# le_strum.net
KiCad netlist of a schematic drawn in EAGLE
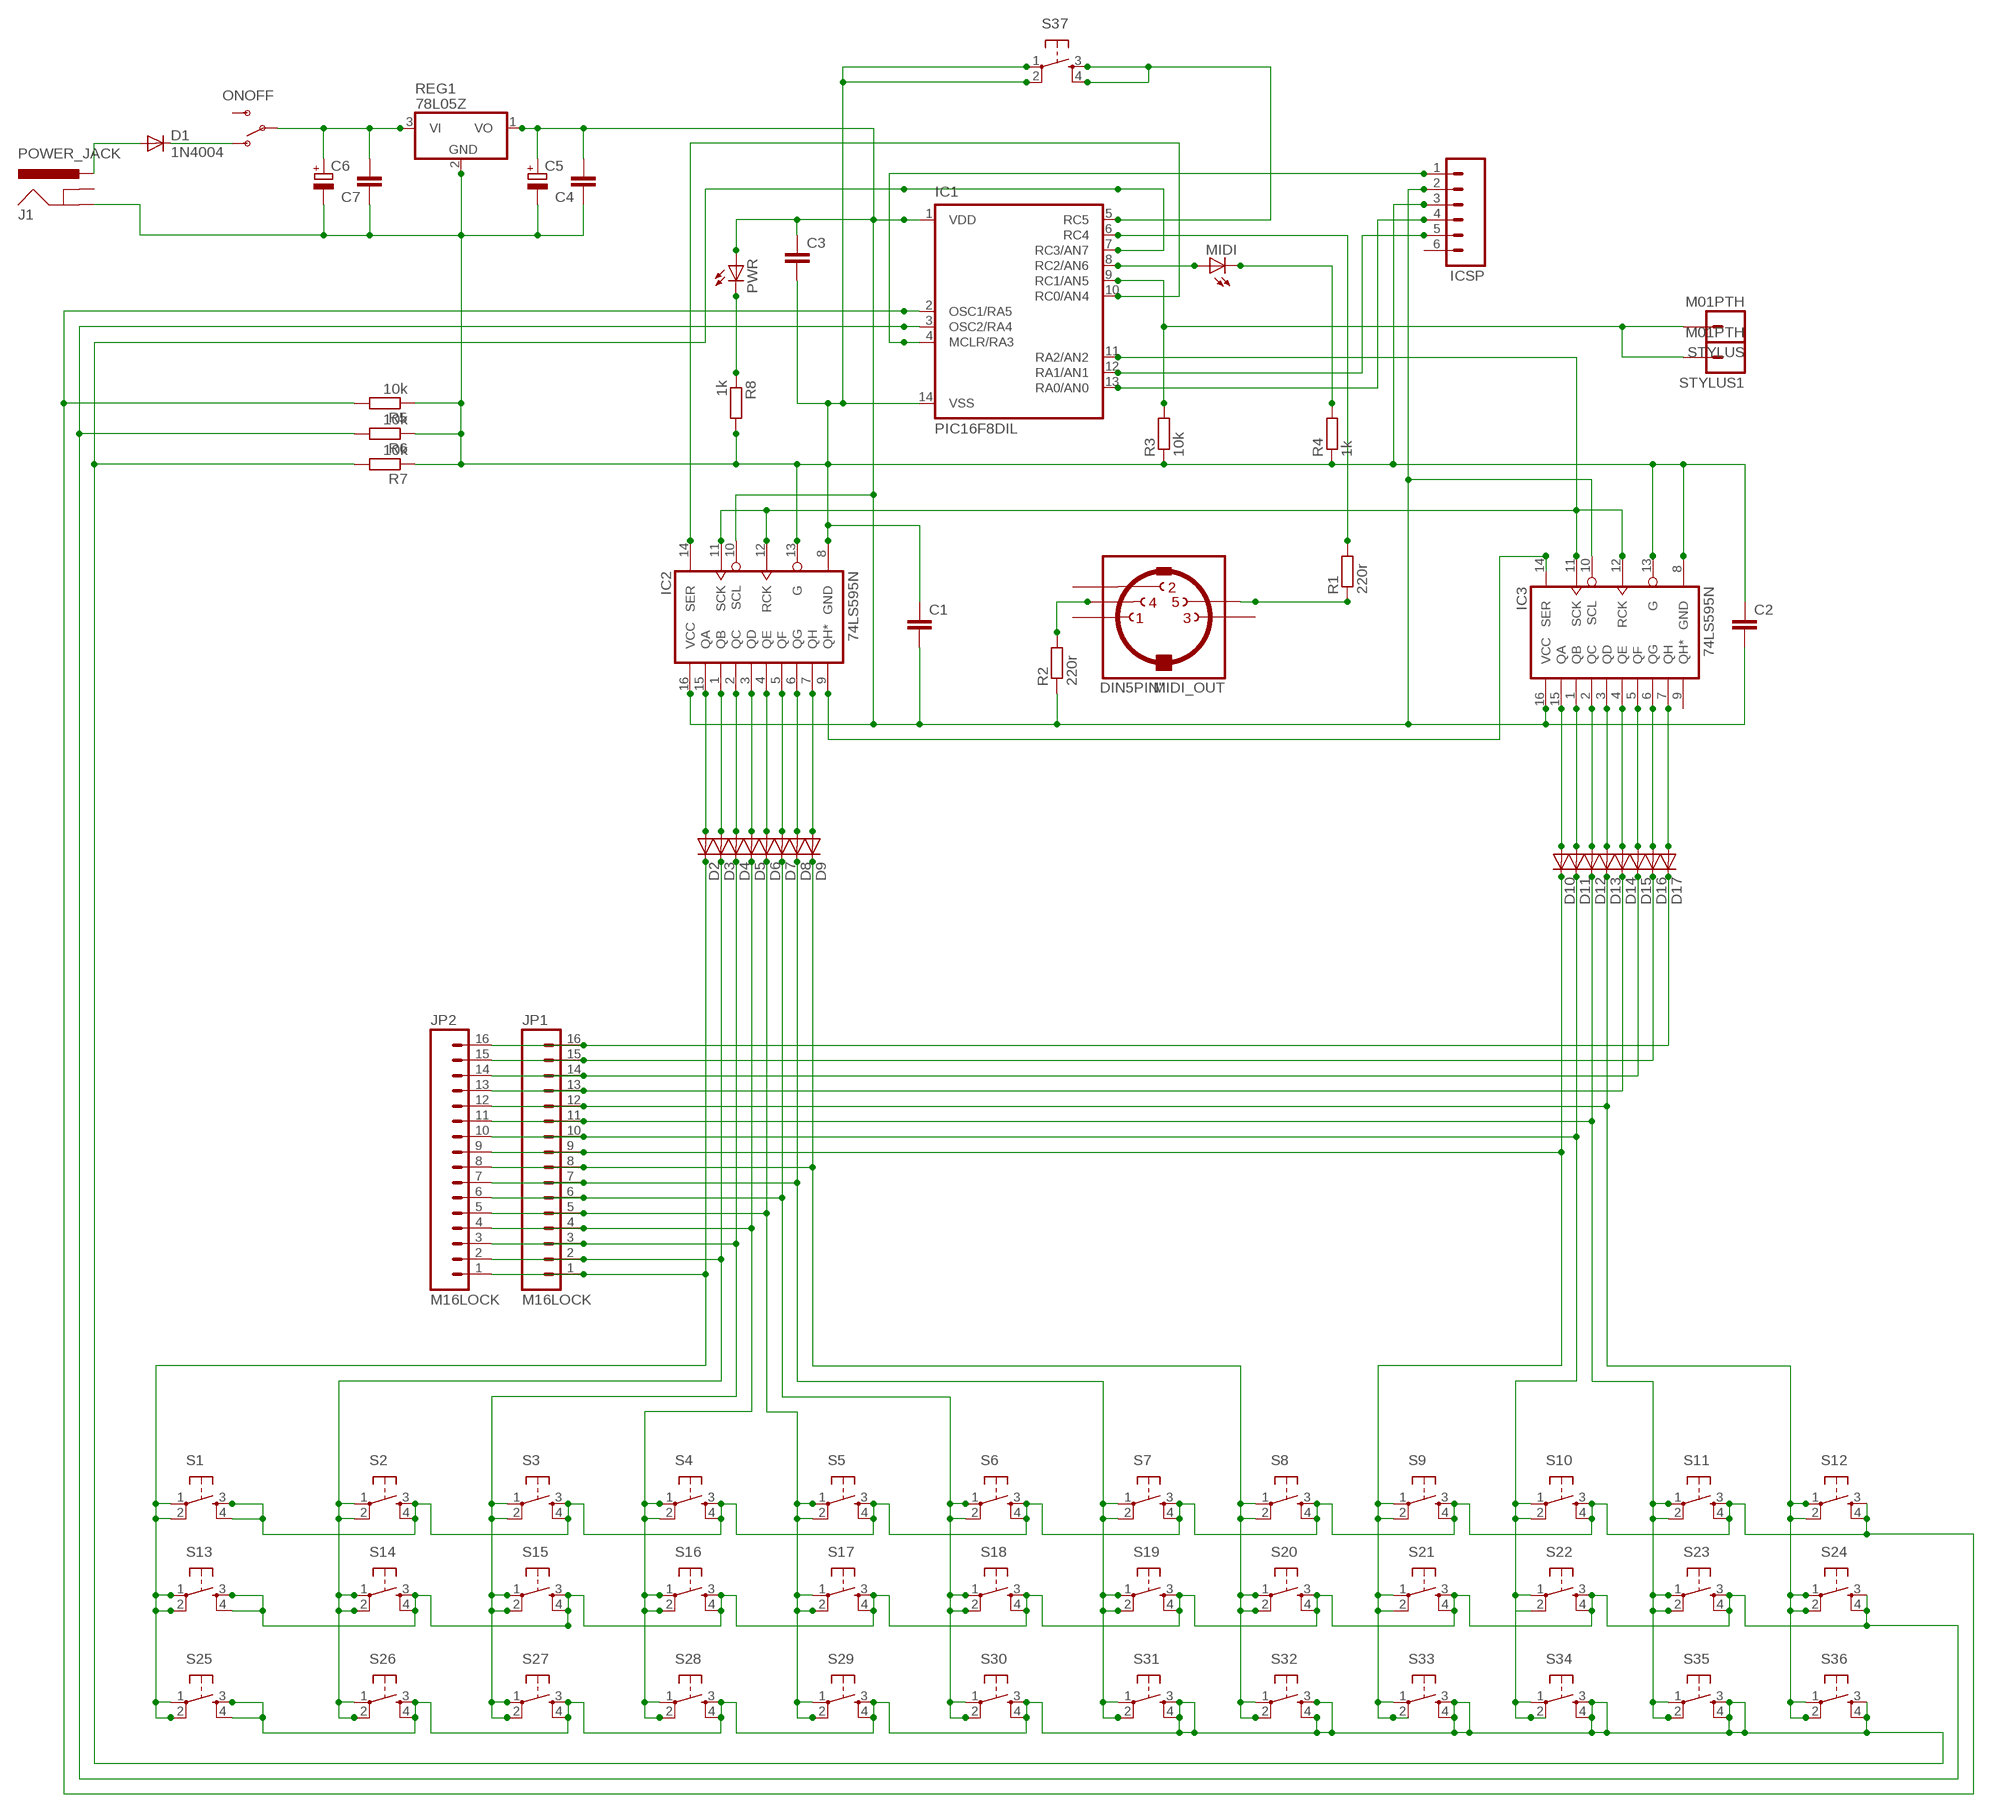
[diagram p0: schematic, sheet 1]

(export (version "E")
  (design (tool "Eeschema 10.0.6"))
  (components
    (comp (ref "C1")
      (value "C-EU025-024X044")
      (footprint "eagle-import:C025-024X044")
      (libsource (lib "eagle-import") (part "C-EU025-024X044"))
    )
    (comp (ref "C2")
      (value "C-EU025-024X044")
      (footprint "eagle-import:C025-024X044")
      (libsource (lib "eagle-import") (part "C-EU025-024X044"))
    )
    (comp (ref "C3")
      (value "C-EU025-024X044")
      (footprint "eagle-import:C025-024X044")
      (libsource (lib "eagle-import") (part "C-EU025-024X044"))
    )
    (comp (ref "C4")
      (value "C-EU025-024X044")
      (footprint "eagle-import:C025-024X044")
      (libsource (lib "eagle-import") (part "C-EU025-024X044"))
    )
    (comp (ref "C5")
      (value "CPOL-EUE2-5")
      (footprint "eagle-import:E2-5")
      (libsource (lib "eagle-import") (part "CPOL-EUE2-5"))
    )
    (comp (ref "C6")
      (value "CPOL-EUE2-5")
      (footprint "eagle-import:E2-5")
      (libsource (lib "eagle-import") (part "CPOL-EUE2-5"))
    )
    (comp (ref "C7")
      (value "C-EU025-024X044")
      (footprint "eagle-import:C025-024X044")
      (libsource (lib "eagle-import") (part "C-EU025-024X044"))
    )
    (comp (ref "D1")
      (value "1N4004")
      (footprint "eagle-import:DO41-10")
      (libsource (lib "eagle-import") (part "1N4004"))
    )
    (comp (ref "D2")
      (value "DIODE-D-5")
      (footprint "eagle-import:D-5")
      (libsource (lib "eagle-import") (part "DIODE-D-5"))
    )
    (comp (ref "D3")
      (value "DIODE-D-5")
      (footprint "eagle-import:D-5")
      (libsource (lib "eagle-import") (part "DIODE-D-5"))
    )
    (comp (ref "D4")
      (value "DIODE-D-5")
      (footprint "eagle-import:D-5")
      (libsource (lib "eagle-import") (part "DIODE-D-5"))
    )
    (comp (ref "D5")
      (value "DIODE-D-5")
      (footprint "eagle-import:D-5")
      (libsource (lib "eagle-import") (part "DIODE-D-5"))
    )
    (comp (ref "D6")
      (value "DIODE-D-5")
      (footprint "eagle-import:D-5")
      (libsource (lib "eagle-import") (part "DIODE-D-5"))
    )
    (comp (ref "D7")
      (value "DIODE-D-5")
      (footprint "eagle-import:D-5")
      (libsource (lib "eagle-import") (part "DIODE-D-5"))
    )
    (comp (ref "D8")
      (value "DIODE-D-5")
      (footprint "eagle-import:D-5")
      (libsource (lib "eagle-import") (part "DIODE-D-5"))
    )
    (comp (ref "D9")
      (value "DIODE-D-5")
      (footprint "eagle-import:D-5")
      (libsource (lib "eagle-import") (part "DIODE-D-5"))
    )
    (comp (ref "D10")
      (value "DIODE-D-5")
      (footprint "eagle-import:D-5")
      (libsource (lib "eagle-import") (part "DIODE-D-5"))
    )
    (comp (ref "D11")
      (value "DIODE-D-5")
      (footprint "eagle-import:D-5")
      (libsource (lib "eagle-import") (part "DIODE-D-5"))
    )
    (comp (ref "D12")
      (value "DIODE-D-5")
      (footprint "eagle-import:D-5")
      (libsource (lib "eagle-import") (part "DIODE-D-5"))
    )
    (comp (ref "D13")
      (value "DIODE-D-5")
      (footprint "eagle-import:D-5")
      (libsource (lib "eagle-import") (part "DIODE-D-5"))
    )
    (comp (ref "D14")
      (value "DIODE-D-5")
      (footprint "eagle-import:D-5")
      (libsource (lib "eagle-import") (part "DIODE-D-5"))
    )
    (comp (ref "D15")
      (value "DIODE-D-5")
      (footprint "eagle-import:D-5")
      (libsource (lib "eagle-import") (part "DIODE-D-5"))
    )
    (comp (ref "D16")
      (value "DIODE-D-5")
      (footprint "eagle-import:D-5")
      (libsource (lib "eagle-import") (part "DIODE-D-5"))
    )
    (comp (ref "D17")
      (value "DIODE-D-5")
      (footprint "eagle-import:D-5")
      (libsource (lib "eagle-import") (part "DIODE-D-5"))
    )
    (comp (ref "IC1")
      (value "PIC16F8DIL")
      (footprint "eagle-import:DIL14")
      (libsource (lib "eagle-import") (part "PIC16F8DIL"))
    )
    (comp (ref "IC2")
      (value "74LS595N")
      (footprint "eagle-import:DIL16")
      (libsource (lib "eagle-import") (part "74595NLS"))
    )
    (comp (ref "IC3")
      (value "74LS595N")
      (footprint "eagle-import:DIL16")
      (libsource (lib "eagle-import") (part "74595NLS"))
    )
    (comp (ref "ICSP")
      (value "M06SIP")
      (footprint "eagle-import:1X06")
      (libsource (lib "eagle-import") (part "M06SIP"))
    )
    (comp (ref "J1")
      (value "POWER_JACK")
      (footprint "eagle-import:POWER_JACK_PTH")
      (libsource (lib "eagle-import") (part "POWER_JACK"))
    )
    (comp (ref "JP1")
      (value "M16LOCK")
      (footprint "eagle-import:1X16_LOCK")
      (libsource (lib "eagle-import") (part "M16LOCK"))
    )
    (comp (ref "JP2")
      (value "M16LOCK")
      (footprint "eagle-import:1X16_LOCK")
      (libsource (lib "eagle-import") (part "M16LOCK"))
    )
    (comp (ref "MIDI")
      (value "LED3MM")
      (footprint "eagle-import:LED3MM")
      (libsource (lib "eagle-import") (part "LED3MM"))
    )
    (comp (ref "MIDI_OUT")
      (value "DIN5PIN\"")
      (footprint "eagle-import:TRUCONN90")
      (libsource (lib "eagle-import") (part "DIN5PIN{dblquote}"))
    )
    (comp (ref "ONOFF")
      (value "SWITCH-SPSTPTH")
      (footprint "eagle-import:SWITCH-SPDT")
      (libsource (lib "eagle-import") (part "SWITCH-SPSTPTH"))
    )
    (comp (ref "PWR")
      (value "LED3MM")
      (footprint "eagle-import:LED3MM")
      (libsource (lib "eagle-import") (part "LED3MM"))
    )
    (comp (ref "R1")
      (value "220r")
      (footprint "eagle-import:0207_7")
      (libsource (lib "eagle-import") (part "R-EU_0207/7"))
    )
    (comp (ref "R2")
      (value "220r")
      (footprint "eagle-import:0207_7")
      (libsource (lib "eagle-import") (part "R-EU_0207/7"))
    )
    (comp (ref "R3")
      (value "10k")
      (footprint "eagle-import:0207_7")
      (libsource (lib "eagle-import") (part "R-EU_0207/7"))
    )
    (comp (ref "R4")
      (value "1k")
      (footprint "eagle-import:0207_7")
      (libsource (lib "eagle-import") (part "R-EU_0207/7"))
    )
    (comp (ref "R5")
      (value "10k")
      (footprint "eagle-import:0207_7")
      (libsource (lib "eagle-import") (part "R-EU_0207/7"))
    )
    (comp (ref "R6")
      (value "10k")
      (footprint "eagle-import:0207_7")
      (libsource (lib "eagle-import") (part "R-EU_0207/7"))
    )
    (comp (ref "R7")
      (value "10k")
      (footprint "eagle-import:0207_7")
      (libsource (lib "eagle-import") (part "R-EU_0207/7"))
    )
    (comp (ref "R8")
      (value "1k")
      (footprint "eagle-import:0207_7")
      (libsource (lib "eagle-import") (part "R-EU_0207/7"))
    )
    (comp (ref "REG1")
      (value "78L05Z")
      (footprint "eagle-import:TO92")
      (libsource (lib "eagle-import") (part "78ZL05"))
    )
    (comp (ref "S1")
      (value "TAC_SWITCHPTH")
      (footprint "eagle-import:TACTILE-PTH")
      (libsource (lib "eagle-import") (part "TAC_SWITCHPTH"))
    )
    (comp (ref "S2")
      (value "TAC_SWITCHPTH")
      (footprint "eagle-import:TACTILE-PTH")
      (libsource (lib "eagle-import") (part "TAC_SWITCHPTH"))
    )
    (comp (ref "S3")
      (value "TAC_SWITCHPTH")
      (footprint "eagle-import:TACTILE-PTH")
      (libsource (lib "eagle-import") (part "TAC_SWITCHPTH"))
    )
    (comp (ref "S4")
      (value "TAC_SWITCHPTH")
      (footprint "eagle-import:TACTILE-PTH")
      (libsource (lib "eagle-import") (part "TAC_SWITCHPTH"))
    )
    (comp (ref "S5")
      (value "TAC_SWITCHPTH")
      (footprint "eagle-import:TACTILE-PTH")
      (libsource (lib "eagle-import") (part "TAC_SWITCHPTH"))
    )
    (comp (ref "S6")
      (value "TAC_SWITCHPTH")
      (footprint "eagle-import:TACTILE-PTH")
      (libsource (lib "eagle-import") (part "TAC_SWITCHPTH"))
    )
    (comp (ref "S7")
      (value "TAC_SWITCHPTH")
      (footprint "eagle-import:TACTILE-PTH")
      (libsource (lib "eagle-import") (part "TAC_SWITCHPTH"))
    )
    (comp (ref "S8")
      (value "TAC_SWITCHPTH")
      (footprint "eagle-import:TACTILE-PTH")
      (libsource (lib "eagle-import") (part "TAC_SWITCHPTH"))
    )
    (comp (ref "S9")
      (value "TAC_SWITCHPTH")
      (footprint "eagle-import:TACTILE-PTH")
      (libsource (lib "eagle-import") (part "TAC_SWITCHPTH"))
    )
    (comp (ref "S10")
      (value "TAC_SWITCHPTH")
      (footprint "eagle-import:TACTILE-PTH")
      (libsource (lib "eagle-import") (part "TAC_SWITCHPTH"))
    )
    (comp (ref "S11")
      (value "TAC_SWITCHPTH")
      (footprint "eagle-import:TACTILE-PTH")
      (libsource (lib "eagle-import") (part "TAC_SWITCHPTH"))
    )
    (comp (ref "S12")
      (value "TAC_SWITCHPTH")
      (footprint "eagle-import:TACTILE-PTH")
      (libsource (lib "eagle-import") (part "TAC_SWITCHPTH"))
    )
    (comp (ref "S13")
      (value "TAC_SWITCHPTH")
      (footprint "eagle-import:TACTILE-PTH")
      (libsource (lib "eagle-import") (part "TAC_SWITCHPTH"))
    )
    (comp (ref "S14")
      (value "TAC_SWITCHPTH")
      (footprint "eagle-import:TACTILE-PTH")
      (libsource (lib "eagle-import") (part "TAC_SWITCHPTH"))
    )
    (comp (ref "S15")
      (value "TAC_SWITCHPTH")
      (footprint "eagle-import:TACTILE-PTH")
      (libsource (lib "eagle-import") (part "TAC_SWITCHPTH"))
    )
    (comp (ref "S16")
      (value "TAC_SWITCHPTH")
      (footprint "eagle-import:TACTILE-PTH")
      (libsource (lib "eagle-import") (part "TAC_SWITCHPTH"))
    )
    (comp (ref "S17")
      (value "TAC_SWITCHPTH")
      (footprint "eagle-import:TACTILE-PTH")
      (libsource (lib "eagle-import") (part "TAC_SWITCHPTH"))
    )
    (comp (ref "S18")
      (value "TAC_SWITCHPTH")
      (footprint "eagle-import:TACTILE-PTH")
      (libsource (lib "eagle-import") (part "TAC_SWITCHPTH"))
    )
    (comp (ref "S19")
      (value "TAC_SWITCHPTH")
      (footprint "eagle-import:TACTILE-PTH")
      (libsource (lib "eagle-import") (part "TAC_SWITCHPTH"))
    )
    (comp (ref "S20")
      (value "TAC_SWITCHPTH")
      (footprint "eagle-import:TACTILE-PTH")
      (libsource (lib "eagle-import") (part "TAC_SWITCHPTH"))
    )
    (comp (ref "S21")
      (value "TAC_SWITCHPTH")
      (footprint "eagle-import:TACTILE-PTH")
      (libsource (lib "eagle-import") (part "TAC_SWITCHPTH"))
    )
    (comp (ref "S22")
      (value "TAC_SWITCHPTH")
      (footprint "eagle-import:TACTILE-PTH")
      (libsource (lib "eagle-import") (part "TAC_SWITCHPTH"))
    )
    (comp (ref "S23")
      (value "TAC_SWITCHPTH")
      (footprint "eagle-import:TACTILE-PTH")
      (libsource (lib "eagle-import") (part "TAC_SWITCHPTH"))
    )
    (comp (ref "S24")
      (value "TAC_SWITCHPTH")
      (footprint "eagle-import:TACTILE-PTH")
      (libsource (lib "eagle-import") (part "TAC_SWITCHPTH"))
    )
    (comp (ref "S25")
      (value "TAC_SWITCHPTH")
      (footprint "eagle-import:TACTILE-PTH")
      (libsource (lib "eagle-import") (part "TAC_SWITCHPTH"))
    )
    (comp (ref "S26")
      (value "TAC_SWITCHPTH")
      (footprint "eagle-import:TACTILE-PTH")
      (libsource (lib "eagle-import") (part "TAC_SWITCHPTH"))
    )
    (comp (ref "S27")
      (value "TAC_SWITCHPTH")
      (footprint "eagle-import:TACTILE-PTH")
      (libsource (lib "eagle-import") (part "TAC_SWITCHPTH"))
    )
    (comp (ref "S28")
      (value "TAC_SWITCHPTH")
      (footprint "eagle-import:TACTILE-PTH")
      (libsource (lib "eagle-import") (part "TAC_SWITCHPTH"))
    )
    (comp (ref "S29")
      (value "TAC_SWITCHPTH")
      (footprint "eagle-import:TACTILE-PTH")
      (libsource (lib "eagle-import") (part "TAC_SWITCHPTH"))
    )
    (comp (ref "S30")
      (value "TAC_SWITCHPTH")
      (footprint "eagle-import:TACTILE-PTH")
      (libsource (lib "eagle-import") (part "TAC_SWITCHPTH"))
    )
    (comp (ref "S31")
      (value "TAC_SWITCHPTH")
      (footprint "eagle-import:TACTILE-PTH")
      (libsource (lib "eagle-import") (part "TAC_SWITCHPTH"))
    )
    (comp (ref "S32")
      (value "TAC_SWITCHPTH")
      (footprint "eagle-import:TACTILE-PTH")
      (libsource (lib "eagle-import") (part "TAC_SWITCHPTH"))
    )
    (comp (ref "S33")
      (value "TAC_SWITCHPTH")
      (footprint "eagle-import:TACTILE-PTH")
      (libsource (lib "eagle-import") (part "TAC_SWITCHPTH"))
    )
    (comp (ref "S34")
      (value "TAC_SWITCHPTH")
      (footprint "eagle-import:TACTILE-PTH")
      (libsource (lib "eagle-import") (part "TAC_SWITCHPTH"))
    )
    (comp (ref "S35")
      (value "TAC_SWITCHPTH")
      (footprint "eagle-import:TACTILE-PTH")
      (libsource (lib "eagle-import") (part "TAC_SWITCHPTH"))
    )
    (comp (ref "S36")
      (value "TAC_SWITCHPTH")
      (footprint "eagle-import:TACTILE-PTH")
      (libsource (lib "eagle-import") (part "TAC_SWITCHPTH"))
    )
    (comp (ref "S37")
      (value "TAC_SWITCHPTH")
      (footprint "eagle-import:TACTILE-PTH")
      (libsource (lib "eagle-import") (part "TAC_SWITCHPTH"))
    )
    (comp (ref "STYLUS")
      (value "M01PTH")
      (footprint "eagle-import:1X01")
      (libsource (lib "eagle-import") (part "M01PTH"))
    )
    (comp (ref "STYLUS1")
      (value "M01PTH")
      (footprint "eagle-import:1X01")
      (libsource (lib "eagle-import") (part "M01PTH"))
    )
  )
  (nets
    (net (code "1") (name "Net-(D1-PadA)") (class "Default")
      (node (ref "D1") (pin "A") (pinfunction "A_A") (pintype "passive"))
      (node (ref "J1") (pin "PWR") (pinfunction "PWR_PWR") (pintype "bidirectional"))
    )
    (net (code "2") (name "Net-(D2-PadC)") (class "Default")
      (node (ref "D2") (pin "C") (pinfunction "C_C") (pintype "passive"))
      (node (ref "JP1") (pin "1") (pinfunction "1_1") (pintype "passive"))
      (node (ref "JP2") (pin "1") (pinfunction "1_1") (pintype "passive"))
      (node (ref "S1") (pin "1") (pinfunction "1_1") (pintype "passive"))
      (node (ref "S1") (pin "2") (pinfunction "2_2") (pintype "passive"))
      (node (ref "S13") (pin "1") (pinfunction "1_1") (pintype "passive"))
      (node (ref "S13") (pin "2") (pinfunction "2_2") (pintype "passive"))
      (node (ref "S25") (pin "1") (pinfunction "1_1") (pintype "passive"))
      (node (ref "S25") (pin "2") (pinfunction "2_2") (pintype "passive"))
    )
    (net (code "3") (name "Net-(D3-PadC)") (class "Default")
      (node (ref "D3") (pin "C") (pinfunction "C_C") (pintype "passive"))
      (node (ref "JP1") (pin "2") (pinfunction "2_2") (pintype "passive"))
      (node (ref "JP2") (pin "2") (pinfunction "2_2") (pintype "passive"))
      (node (ref "S14") (pin "1") (pinfunction "1_1") (pintype "passive"))
      (node (ref "S14") (pin "2") (pinfunction "2_2") (pintype "passive"))
      (node (ref "S2") (pin "1") (pinfunction "1_1") (pintype "passive"))
      (node (ref "S2") (pin "2") (pinfunction "2_2") (pintype "passive"))
      (node (ref "S26") (pin "1") (pinfunction "1_1") (pintype "passive"))
      (node (ref "S26") (pin "2") (pinfunction "2_2") (pintype "passive"))
    )
    (net (code "4") (name "Net-(D4-PadC)") (class "Default")
      (node (ref "D4") (pin "C") (pinfunction "C_C") (pintype "passive"))
      (node (ref "JP1") (pin "3") (pinfunction "3_3") (pintype "passive"))
      (node (ref "JP2") (pin "3") (pinfunction "3_3") (pintype "passive"))
      (node (ref "S15") (pin "1") (pinfunction "1_1") (pintype "passive"))
      (node (ref "S15") (pin "2") (pinfunction "2_2") (pintype "passive"))
      (node (ref "S27") (pin "1") (pinfunction "1_1") (pintype "passive"))
      (node (ref "S27") (pin "2") (pinfunction "2_2") (pintype "passive"))
      (node (ref "S3") (pin "1") (pinfunction "1_1") (pintype "passive"))
      (node (ref "S3") (pin "2") (pinfunction "2_2") (pintype "passive"))
    )
    (net (code "5") (name "Net-(D5-PadC)") (class "Default")
      (node (ref "D5") (pin "C") (pinfunction "C_C") (pintype "passive"))
      (node (ref "JP1") (pin "4") (pinfunction "4_4") (pintype "passive"))
      (node (ref "JP2") (pin "4") (pinfunction "4_4") (pintype "passive"))
      (node (ref "S16") (pin "1") (pinfunction "1_1") (pintype "passive"))
      (node (ref "S16") (pin "2") (pinfunction "2_2") (pintype "passive"))
      (node (ref "S28") (pin "1") (pinfunction "1_1") (pintype "passive"))
      (node (ref "S28") (pin "2") (pinfunction "2_2") (pintype "passive"))
      (node (ref "S4") (pin "1") (pinfunction "1_1") (pintype "passive"))
      (node (ref "S4") (pin "2") (pinfunction "2_2") (pintype "passive"))
    )
    (net (code "6") (name "Net-(D6-PadC)") (class "Default")
      (node (ref "D6") (pin "C") (pinfunction "C_C") (pintype "passive"))
      (node (ref "JP1") (pin "5") (pinfunction "5_5") (pintype "passive"))
      (node (ref "JP2") (pin "5") (pinfunction "5_5") (pintype "passive"))
      (node (ref "S17") (pin "1") (pinfunction "1_1") (pintype "passive"))
      (node (ref "S17") (pin "2") (pinfunction "2_2") (pintype "passive"))
      (node (ref "S29") (pin "1") (pinfunction "1_1") (pintype "passive"))
      (node (ref "S29") (pin "2") (pinfunction "2_2") (pintype "passive"))
      (node (ref "S5") (pin "1") (pinfunction "1_1") (pintype "passive"))
      (node (ref "S5") (pin "2") (pinfunction "2_2") (pintype "passive"))
    )
    (net (code "7") (name "Net-(D7-PadC)") (class "Default")
      (node (ref "D7") (pin "C") (pinfunction "C_C") (pintype "passive"))
      (node (ref "JP1") (pin "6") (pinfunction "6_6") (pintype "passive"))
      (node (ref "JP2") (pin "6") (pinfunction "6_6") (pintype "passive"))
      (node (ref "S18") (pin "1") (pinfunction "1_1") (pintype "passive"))
      (node (ref "S18") (pin "2") (pinfunction "2_2") (pintype "passive"))
      (node (ref "S30") (pin "1") (pinfunction "1_1") (pintype "passive"))
      (node (ref "S30") (pin "2") (pinfunction "2_2") (pintype "passive"))
      (node (ref "S6") (pin "1") (pinfunction "1_1") (pintype "passive"))
      (node (ref "S6") (pin "2") (pinfunction "2_2") (pintype "passive"))
    )
    (net (code "8") (name "Net-(D8-PadC)") (class "Default")
      (node (ref "D8") (pin "C") (pinfunction "C_C") (pintype "passive"))
      (node (ref "JP1") (pin "7") (pinfunction "7_7") (pintype "passive"))
      (node (ref "JP2") (pin "7") (pinfunction "7_7") (pintype "passive"))
      (node (ref "S19") (pin "1") (pinfunction "1_1") (pintype "passive"))
      (node (ref "S19") (pin "2") (pinfunction "2_2") (pintype "passive"))
      (node (ref "S31") (pin "1") (pinfunction "1_1") (pintype "passive"))
      (node (ref "S31") (pin "2") (pinfunction "2_2") (pintype "passive"))
      (node (ref "S7") (pin "1") (pinfunction "1_1") (pintype "passive"))
      (node (ref "S7") (pin "2") (pinfunction "2_2") (pintype "passive"))
    )
    (net (code "9") (name "Net-(D9-PadC)") (class "Default")
      (node (ref "D9") (pin "C") (pinfunction "C_C") (pintype "passive"))
      (node (ref "JP1") (pin "8") (pinfunction "8_8") (pintype "passive"))
      (node (ref "JP2") (pin "8") (pinfunction "8_8") (pintype "passive"))
      (node (ref "S20") (pin "1") (pinfunction "1_1") (pintype "passive"))
      (node (ref "S20") (pin "2") (pinfunction "2_2") (pintype "passive"))
      (node (ref "S32") (pin "1") (pinfunction "1_1") (pintype "passive"))
      (node (ref "S32") (pin "2") (pinfunction "2_2") (pintype "passive"))
      (node (ref "S8") (pin "1") (pinfunction "1_1") (pintype "passive"))
      (node (ref "S8") (pin "2") (pinfunction "2_2") (pintype "passive"))
    )
    (net (code "10") (name "Net-(D10-PadC)") (class "Default")
      (node (ref "D10") (pin "C") (pinfunction "C_C") (pintype "passive"))
      (node (ref "JP1") (pin "9") (pinfunction "9_9") (pintype "passive"))
      (node (ref "JP2") (pin "9") (pinfunction "9_9") (pintype "passive"))
      (node (ref "S21") (pin "1") (pinfunction "1_1") (pintype "passive"))
      (node (ref "S21") (pin "2") (pinfunction "2_2") (pintype "passive"))
      (node (ref "S33") (pin "1") (pinfunction "1_1") (pintype "passive"))
      (node (ref "S33") (pin "2") (pinfunction "2_2") (pintype "passive"))
      (node (ref "S9") (pin "1") (pinfunction "1_1") (pintype "passive"))
      (node (ref "S9") (pin "2") (pinfunction "2_2") (pintype "passive"))
    )
    (net (code "11") (name "Net-(D11-PadC)") (class "Default")
      (node (ref "D11") (pin "C") (pinfunction "C_C") (pintype "passive"))
      (node (ref "JP1") (pin "10") (pinfunction "10_10") (pintype "passive"))
      (node (ref "JP2") (pin "10") (pinfunction "10_10") (pintype "passive"))
      (node (ref "S10") (pin "1") (pinfunction "1_1") (pintype "passive"))
      (node (ref "S10") (pin "2") (pinfunction "2_2") (pintype "passive"))
      (node (ref "S22") (pin "1") (pinfunction "1_1") (pintype "passive"))
      (node (ref "S22") (pin "2") (pinfunction "2_2") (pintype "passive"))
      (node (ref "S34") (pin "1") (pinfunction "1_1") (pintype "passive"))
      (node (ref "S34") (pin "2") (pinfunction "2_2") (pintype "passive"))
    )
    (net (code "12") (name "Net-(D12-PadC)") (class "Default")
      (node (ref "D12") (pin "C") (pinfunction "C_C") (pintype "passive"))
      (node (ref "JP1") (pin "11") (pinfunction "11_11") (pintype "passive"))
      (node (ref "JP2") (pin "11") (pinfunction "11_11") (pintype "passive"))
      (node (ref "S11") (pin "1") (pinfunction "1_1") (pintype "passive"))
      (node (ref "S11") (pin "2") (pinfunction "2_2") (pintype "passive"))
      (node (ref "S23") (pin "1") (pinfunction "1_1") (pintype "passive"))
      (node (ref "S23") (pin "2") (pinfunction "2_2") (pintype "passive"))
      (node (ref "S35") (pin "1") (pinfunction "1_1") (pintype "passive"))
      (node (ref "S35") (pin "2") (pinfunction "2_2") (pintype "passive"))
    )
    (net (code "13") (name "Net-(D13-PadC)") (class "Default")
      (node (ref "D13") (pin "C") (pinfunction "C_C") (pintype "passive"))
      (node (ref "JP1") (pin "12") (pinfunction "12_12") (pintype "passive"))
      (node (ref "JP2") (pin "12") (pinfunction "12_12") (pintype "passive"))
      (node (ref "S12") (pin "1") (pinfunction "1_1") (pintype "passive"))
      (node (ref "S12") (pin "2") (pinfunction "2_2") (pintype "passive"))
      (node (ref "S24") (pin "1") (pinfunction "1_1") (pintype "passive"))
      (node (ref "S24") (pin "2") (pinfunction "2_2") (pintype "passive"))
      (node (ref "S36") (pin "1") (pinfunction "1_1") (pintype "passive"))
      (node (ref "S36") (pin "2") (pinfunction "2_2") (pintype "passive"))
    )
    (net (code "14") (name "Net-(D14-PadC)") (class "Default")
      (node (ref "D14") (pin "C") (pinfunction "C_C") (pintype "passive"))
      (node (ref "JP1") (pin "13") (pinfunction "13_13") (pintype "passive"))
      (node (ref "JP2") (pin "13") (pinfunction "13_13") (pintype "passive"))
    )
    (net (code "15") (name "Net-(D15-PadC)") (class "Default")
      (node (ref "D15") (pin "C") (pinfunction "C_C") (pintype "passive"))
      (node (ref "JP1") (pin "14") (pinfunction "14_14") (pintype "passive"))
      (node (ref "JP2") (pin "14") (pinfunction "14_14") (pintype "passive"))
    )
    (net (code "16") (name "Net-(D16-PadC)") (class "Default")
      (node (ref "D16") (pin "C") (pinfunction "C_C") (pintype "passive"))
      (node (ref "JP1") (pin "15") (pinfunction "15_15") (pintype "passive"))
      (node (ref "JP2") (pin "15") (pinfunction "15_15") (pintype "passive"))
    )
    (net (code "17") (name "Net-(D17-PadC)") (class "Default")
      (node (ref "D17") (pin "C") (pinfunction "C_C") (pintype "passive"))
      (node (ref "JP1") (pin "16") (pinfunction "16_16") (pintype "passive"))
      (node (ref "JP2") (pin "16") (pinfunction "16_16") (pintype "passive"))
    )
    (net (code "18") (name "Net-(IC1-MCLR{slash}RA3)") (class "Default")
      (node (ref "IC1") (pin "4") (pinfunction "MCLR/RA3_4") (pintype "input"))
      (node (ref "ICSP") (pin "1") (pinfunction "1_1") (pintype "passive"))
    )
    (net (code "19") (name "Net-(IC1-OSC1{slash}RA5)") (class "Default")
      (node (ref "IC1") (pin "2") (pinfunction "OSC1/RA5_2") (pintype "input"))
      (node (ref "R5") (pin "2") (pinfunction "2_2") (pintype "passive"))
      (node (ref "S1") (pin "3") (pinfunction "3_3") (pintype "passive"))
      (node (ref "S1") (pin "4") (pinfunction "4_4") (pintype "passive"))
      (node (ref "S10") (pin "3") (pinfunction "3_3") (pintype "passive"))
      (node (ref "S10") (pin "4") (pinfunction "4_4") (pintype "passive"))
      (node (ref "S11") (pin "3") (pinfunction "3_3") (pintype "passive"))
      (node (ref "S11") (pin "4") (pinfunction "4_4") (pintype "passive"))
      (node (ref "S12") (pin "3") (pinfunction "3_3") (pintype "passive"))
      (node (ref "S12") (pin "4") (pinfunction "4_4") (pintype "passive"))
      (node (ref "S2") (pin "3") (pinfunction "3_3") (pintype "passive"))
      (node (ref "S2") (pin "4") (pinfunction "4_4") (pintype "passive"))
      (node (ref "S3") (pin "3") (pinfunction "3_3") (pintype "passive"))
      (node (ref "S3") (pin "4") (pinfunction "4_4") (pintype "passive"))
      (node (ref "S4") (pin "3") (pinfunction "3_3") (pintype "passive"))
      (node (ref "S4") (pin "4") (pinfunction "4_4") (pintype "passive"))
      (node (ref "S5") (pin "3") (pinfunction "3_3") (pintype "passive"))
      (node (ref "S5") (pin "4") (pinfunction "4_4") (pintype "passive"))
      (node (ref "S6") (pin "3") (pinfunction "3_3") (pintype "passive"))
      (node (ref "S6") (pin "4") (pinfunction "4_4") (pintype "passive"))
      (node (ref "S7") (pin "3") (pinfunction "3_3") (pintype "passive"))
      (node (ref "S7") (pin "4") (pinfunction "4_4") (pintype "passive"))
      (node (ref "S8") (pin "3") (pinfunction "3_3") (pintype "passive"))
      (node (ref "S8") (pin "4") (pinfunction "4_4") (pintype "passive"))
      (node (ref "S9") (pin "3") (pinfunction "3_3") (pintype "passive"))
      (node (ref "S9") (pin "4") (pinfunction "4_4") (pintype "passive"))
    )
    (net (code "20") (name "Net-(IC1-OSC2{slash}RA4)") (class "Default")
      (node (ref "IC1") (pin "3") (pinfunction "OSC2/RA4_3") (pintype "output"))
      (node (ref "R6") (pin "2") (pinfunction "2_2") (pintype "passive"))
      (node (ref "S13") (pin "3") (pinfunction "3_3") (pintype "passive"))
      (node (ref "S13") (pin "4") (pinfunction "4_4") (pintype "passive"))
      (node (ref "S14") (pin "3") (pinfunction "3_3") (pintype "passive"))
      (node (ref "S14") (pin "4") (pinfunction "4_4") (pintype "passive"))
      (node (ref "S15") (pin "3") (pinfunction "3_3") (pintype "passive"))
      (node (ref "S15") (pin "4") (pinfunction "4_4") (pintype "passive"))
      (node (ref "S16") (pin "3") (pinfunction "3_3") (pintype "passive"))
      (node (ref "S16") (pin "4") (pinfunction "4_4") (pintype "passive"))
      (node (ref "S17") (pin "3") (pinfunction "3_3") (pintype "passive"))
      (node (ref "S17") (pin "4") (pinfunction "4_4") (pintype "passive"))
      (node (ref "S18") (pin "3") (pinfunction "3_3") (pintype "passive"))
      (node (ref "S18") (pin "4") (pinfunction "4_4") (pintype "passive"))
      (node (ref "S19") (pin "3") (pinfunction "3_3") (pintype "passive"))
      (node (ref "S19") (pin "4") (pinfunction "4_4") (pintype "passive"))
      (node (ref "S20") (pin "3") (pinfunction "3_3") (pintype "passive"))
      (node (ref "S20") (pin "4") (pinfunction "4_4") (pintype "passive"))
      (node (ref "S21") (pin "3") (pinfunction "3_3") (pintype "passive"))
      (node (ref "S21") (pin "4") (pinfunction "4_4") (pintype "passive"))
      (node (ref "S22") (pin "3") (pinfunction "3_3") (pintype "passive"))
      (node (ref "S22") (pin "4") (pinfunction "4_4") (pintype "passive"))
      (node (ref "S23") (pin "3") (pinfunction "3_3") (pintype "passive"))
      (node (ref "S23") (pin "4") (pinfunction "4_4") (pintype "passive"))
      (node (ref "S24") (pin "3") (pinfunction "3_3") (pintype "passive"))
      (node (ref "S24") (pin "4") (pinfunction "4_4") (pintype "passive"))
    )
    (net (code "21") (name "Net-(IC1-RA0{slash}AN0)") (class "Default")
      (node (ref "IC1") (pin "13") (pinfunction "RA0/AN0_13") (pintype "bidirectional"))
      (node (ref "ICSP") (pin "4") (pinfunction "4_4") (pintype "passive"))
    )
    (net (code "22") (name "Net-(IC1-RA1{slash}AN1)") (class "Default")
      (node (ref "IC1") (pin "12") (pinfunction "RA1/AN1_12") (pintype "bidirectional"))
      (node (ref "ICSP") (pin "5") (pinfunction "5_5") (pintype "passive"))
    )
    (net (code "23") (name "Net-(IC1-RA2{slash}AN2)") (class "Default")
      (node (ref "IC1") (pin "11") (pinfunction "RA2/AN2_11") (pintype "bidirectional"))
      (node (ref "IC2") (pin "11") (pinfunction "SCK_11") (pintype "input"))
      (node (ref "IC2") (pin "12") (pinfunction "RCK_12") (pintype "input"))
      (node (ref "IC3") (pin "11") (pinfunction "SCK_11") (pintype "input"))
      (node (ref "IC3") (pin "12") (pinfunction "RCK_12") (pintype "input"))
    )
    (net (code "24") (name "Net-(IC1-RC0{slash}AN4)") (class "Default")
      (node (ref "IC1") (pin "10") (pinfunction "RC0/AN4_10") (pintype "bidirectional"))
      (node (ref "IC2") (pin "14") (pinfunction "SER_14") (pintype "input"))
    )
    (net (code "25") (name "Net-(IC1-RC1{slash}AN5)") (class "Default")
      (node (ref "IC1") (pin "9") (pinfunction "RC1/AN5_9") (pintype "bidirectional"))
      (node (ref "R3") (pin "2") (pinfunction "2_2") (pintype "passive"))
      (node (ref "STYLUS") (pin "1") (pinfunction "1_1") (pintype "passive"))
      (node (ref "STYLUS1") (pin "1") (pinfunction "1_1") (pintype "passive"))
    )
    (net (code "26") (name "Net-(IC1-RC2{slash}AN6)") (class "Default")
      (node (ref "IC1") (pin "8") (pinfunction "RC2/AN6_8") (pintype "bidirectional"))
      (node (ref "MIDI") (pin "A") (pinfunction "A_A") (pintype "passive"))
    )
    (net (code "27") (name "Net-(IC1-RC3{slash}AN7)") (class "Default")
      (node (ref "IC1") (pin "7") (pinfunction "RC3/AN7_7") (pintype "bidirectional"))
      (node (ref "R7") (pin "2") (pinfunction "2_2") (pintype "passive"))
      (node (ref "S25") (pin "3") (pinfunction "3_3") (pintype "passive"))
      (node (ref "S25") (pin "4") (pinfunction "4_4") (pintype "passive"))
      (node (ref "S26") (pin "3") (pinfunction "3_3") (pintype "passive"))
      (node (ref "S26") (pin "4") (pinfunction "4_4") (pintype "passive"))
      (node (ref "S27") (pin "3") (pinfunction "3_3") (pintype "passive"))
      (node (ref "S27") (pin "4") (pinfunction "4_4") (pintype "passive"))
      (node (ref "S28") (pin "3") (pinfunction "3_3") (pintype "passive"))
      (node (ref "S28") (pin "4") (pinfunction "4_4") (pintype "passive"))
      (node (ref "S29") (pin "3") (pinfunction "3_3") (pintype "passive"))
      (node (ref "S29") (pin "4") (pinfunction "4_4") (pintype "passive"))
      (node (ref "S30") (pin "3") (pinfunction "3_3") (pintype "passive"))
      (node (ref "S30") (pin "4") (pinfunction "4_4") (pintype "passive"))
      (node (ref "S31") (pin "3") (pinfunction "3_3") (pintype "passive"))
      (node (ref "S31") (pin "4") (pinfunction "4_4") (pintype "passive"))
      (node (ref "S32") (pin "3") (pinfunction "3_3") (pintype "passive"))
      (node (ref "S32") (pin "4") (pinfunction "4_4") (pintype "passive"))
      (node (ref "S33") (pin "3") (pinfunction "3_3") (pintype "passive"))
      (node (ref "S33") (pin "4") (pinfunction "4_4") (pintype "passive"))
      (node (ref "S34") (pin "3") (pinfunction "3_3") (pintype "passive"))
      (node (ref "S34") (pin "4") (pinfunction "4_4") (pintype "passive"))
      (node (ref "S35") (pin "3") (pinfunction "3_3") (pintype "passive"))
      (node (ref "S35") (pin "4") (pinfunction "4_4") (pintype "passive"))
      (node (ref "S36") (pin "3") (pinfunction "3_3") (pintype "passive"))
      (node (ref "S36") (pin "4") (pinfunction "4_4") (pintype "passive"))
    )
    (net (code "28") (name "Net-(IC1-RC4)") (class "Default")
      (node (ref "IC1") (pin "6") (pinfunction "RC4_6") (pintype "bidirectional"))
      (node (ref "R1") (pin "2") (pinfunction "2_2") (pintype "passive"))
    )
    (net (code "29") (name "Net-(IC1-RC5)") (class "Default")
      (node (ref "IC1") (pin "5") (pinfunction "RC5_5") (pintype "bidirectional"))
      (node (ref "S37") (pin "3") (pinfunction "3_3") (pintype "passive"))
      (node (ref "S37") (pin "4") (pinfunction "4_4") (pintype "passive"))
    )
    (net (code "30") (name "Net-(IC1-VDD)") (class "Default")
      (node (ref "C1") (pin "2") (pinfunction "2_2") (pintype "passive"))
      (node (ref "C2") (pin "2") (pinfunction "2_2") (pintype "passive"))
      (node (ref "C3") (pin "1") (pinfunction "1_1") (pintype "passive"))
      (node (ref "C4") (pin "2") (pinfunction "2_2") (pintype "passive"))
      (node (ref "C5") (pin "+") (pinfunction "+_+") (pintype "passive"))
      (node (ref "IC1") (pin "1") (pinfunction "VDD_1") (pintype "power_in"))
      (node (ref "IC2") (pin "10") (pinfunction "SCL_10") (pintype "input"))
      (node (ref "IC2") (pin "16") (pinfunction "VCC_16") (pintype "power_in"))
      (node (ref "IC3") (pin "10") (pinfunction "SCL_10") (pintype "input"))
      (node (ref "IC3") (pin "16") (pinfunction "VCC_16") (pintype "power_in"))
      (node (ref "ICSP") (pin "2") (pinfunction "2_2") (pintype "passive"))
      (node (ref "PWR") (pin "A") (pinfunction "A_A") (pintype "passive"))
      (node (ref "R2") (pin "1") (pinfunction "1_1") (pintype "passive"))
      (node (ref "REG1") (pin "1") (pinfunction "VO_1") (pintype "passive"))
    )
    (net (code "31") (name "Net-(IC1-VSS)") (class "Default")
      (node (ref "C1") (pin "1") (pinfunction "1_1") (pintype "passive"))
      (node (ref "C2") (pin "1") (pinfunction "1_1") (pintype "passive"))
      (node (ref "C3") (pin "2") (pinfunction "2_2") (pintype "passive"))
      (node (ref "C4") (pin "1") (pinfunction "1_1") (pintype "passive"))
      (node (ref "C5") (pin "-") (pinfunction "-_-") (pintype "passive"))
      (node (ref "C6") (pin "-") (pinfunction "-_-") (pintype "passive"))
      (node (ref "C7") (pin "1") (pinfunction "1_1") (pintype "passive"))
      (node (ref "IC1") (pin "14") (pinfunction "VSS_14") (pintype "power_in"))
      (node (ref "IC2") (pin "13") (pinfunction "G_13") (pintype "input"))
      (node (ref "IC2") (pin "8") (pinfunction "GND_8") (pintype "power_in"))
      (node (ref "IC3") (pin "13") (pinfunction "G_13") (pintype "input"))
      (node (ref "IC3") (pin "8") (pinfunction "GND_8") (pintype "power_in"))
      (node (ref "ICSP") (pin "3") (pinfunction "3_3") (pintype "passive"))
      (node (ref "J1") (pin "GND") (pinfunction "GND_GND") (pintype "bidirectional"))
      (node (ref "R3") (pin "1") (pinfunction "1_1") (pintype "passive"))
      (node (ref "R4") (pin "1") (pinfunction "1_1") (pintype "passive"))
      (node (ref "R5") (pin "1") (pinfunction "1_1") (pintype "passive"))
      (node (ref "R6") (pin "1") (pinfunction "1_1") (pintype "passive"))
      (node (ref "R7") (pin "1") (pinfunction "1_1") (pintype "passive"))
      (node (ref "R8") (pin "2") (pinfunction "2_2") (pintype "passive"))
      (node (ref "REG1") (pin "2") (pinfunction "GND_2") (pintype "passive"))
      (node (ref "S37") (pin "1") (pinfunction "1_1") (pintype "passive"))
      (node (ref "S37") (pin "2") (pinfunction "2_2") (pintype "passive"))
    )
    (net (code "32") (name "Net-(IC2-QA)") (class "Default")
      (node (ref "D2") (pin "A") (pinfunction "A_A") (pintype "passive"))
      (node (ref "IC2") (pin "15") (pinfunction "QA_15") (pintype "tri_state"))
    )
    (net (code "33") (name "Net-(IC2-QB)") (class "Default")
      (node (ref "D3") (pin "A") (pinfunction "A_A") (pintype "passive"))
      (node (ref "IC2") (pin "1") (pinfunction "QB_1") (pintype "tri_state"))
    )
    (net (code "34") (name "Net-(IC2-QC)") (class "Default")
      (node (ref "D4") (pin "A") (pinfunction "A_A") (pintype "passive"))
      (node (ref "IC2") (pin "2") (pinfunction "QC_2") (pintype "tri_state"))
    )
    (net (code "35") (name "Net-(IC2-QD)") (class "Default")
      (node (ref "D5") (pin "A") (pinfunction "A_A") (pintype "passive"))
      (node (ref "IC2") (pin "3") (pinfunction "QD_3") (pintype "tri_state"))
    )
    (net (code "36") (name "Net-(IC2-QE)") (class "Default")
      (node (ref "D6") (pin "A") (pinfunction "A_A") (pintype "passive"))
      (node (ref "IC2") (pin "4") (pinfunction "QE_4") (pintype "tri_state"))
    )
    (net (code "37") (name "Net-(IC2-QF)") (class "Default")
      (node (ref "D7") (pin "A") (pinfunction "A_A") (pintype "passive"))
      (node (ref "IC2") (pin "5") (pinfunction "QF_5") (pintype "tri_state"))
    )
    (net (code "38") (name "Net-(IC2-QG)") (class "Default")
      (node (ref "D8") (pin "A") (pinfunction "A_A") (pintype "passive"))
      (node (ref "IC2") (pin "6") (pinfunction "QG_6") (pintype "tri_state"))
    )
    (net (code "39") (name "Net-(IC2-QH)") (class "Default")
      (node (ref "D9") (pin "A") (pinfunction "A_A") (pintype "passive"))
      (node (ref "IC2") (pin "7") (pinfunction "QH_7") (pintype "tri_state"))
    )
    (net (code "40") (name "Net-(IC2-QH*)") (class "Default")
      (node (ref "IC2") (pin "9") (pinfunction "QH*_9") (pintype "tri_state"))
      (node (ref "IC3") (pin "14") (pinfunction "SER_14") (pintype "input"))
    )
    (net (code "41") (name "Net-(IC3-QA)") (class "Default")
      (node (ref "D10") (pin "A") (pinfunction "A_A") (pintype "passive"))
      (node (ref "IC3") (pin "15") (pinfunction "QA_15") (pintype "tri_state"))
    )
    (net (code "42") (name "Net-(IC3-QB)") (class "Default")
      (node (ref "D11") (pin "A") (pinfunction "A_A") (pintype "passive"))
      (node (ref "IC3") (pin "1") (pinfunction "QB_1") (pintype "tri_state"))
    )
    (net (code "43") (name "Net-(IC3-QC)") (class "Default")
      (node (ref "D12") (pin "A") (pinfunction "A_A") (pintype "passive"))
      (node (ref "IC3") (pin "2") (pinfunction "QC_2") (pintype "tri_state"))
    )
    (net (code "44") (name "Net-(IC3-QD)") (class "Default")
      (node (ref "D13") (pin "A") (pinfunction "A_A") (pintype "passive"))
      (node (ref "IC3") (pin "3") (pinfunction "QD_3") (pintype "tri_state"))
    )
    (net (code "45") (name "Net-(IC3-QE)") (class "Default")
      (node (ref "D14") (pin "A") (pinfunction "A_A") (pintype "passive"))
      (node (ref "IC3") (pin "4") (pinfunction "QE_4") (pintype "tri_state"))
    )
    (net (code "46") (name "Net-(IC3-QF)") (class "Default")
      (node (ref "D15") (pin "A") (pinfunction "A_A") (pintype "passive"))
      (node (ref "IC3") (pin "5") (pinfunction "QF_5") (pintype "tri_state"))
    )
    (net (code "47") (name "Net-(IC3-QG)") (class "Default")
      (node (ref "D16") (pin "A") (pinfunction "A_A") (pintype "passive"))
      (node (ref "IC3") (pin "6") (pinfunction "QG_6") (pintype "tri_state"))
    )
    (net (code "48") (name "Net-(IC3-QH)") (class "Default")
      (node (ref "D17") (pin "A") (pinfunction "A_A") (pintype "passive"))
      (node (ref "IC3") (pin "7") (pinfunction "QH_7") (pintype "tri_state"))
    )
    (net (code "49") (name "Net-(MIDI-C)") (class "Default")
      (node (ref "MIDI") (pin "K") (pinfunction "C_K") (pintype "passive"))
      (node (ref "R4") (pin "2") (pinfunction "2_2") (pintype "passive"))
    )
    (net (code "50") (name "Net-(MIDI_OUT-Pad4)") (class "Default")
      (node (ref "MIDI_OUT") (pin "4") (pinfunction "4_4") (pintype "passive"))
      (node (ref "R2") (pin "2") (pinfunction "2_2") (pintype "passive"))
    )
    (net (code "51") (name "Net-(MIDI_OUT-Pad5)") (class "Default")
      (node (ref "MIDI_OUT") (pin "5") (pinfunction "5_5") (pintype "passive"))
      (node (ref "R1") (pin "1") (pinfunction "1_1") (pintype "passive"))
    )
    (net (code "52") (name "Net-(ONOFF-O)") (class "Default")
      (node (ref "D1") (pin "C") (pinfunction "C_C") (pintype "passive"))
      (node (ref "ONOFF") (pin "1") (pinfunction "O_1") (pintype "passive"))
    )
    (net (code "53") (name "Net-(ONOFF-P)") (class "Default")
      (node (ref "C6") (pin "+") (pinfunction "+_+") (pintype "passive"))
      (node (ref "C7") (pin "2") (pinfunction "2_2") (pintype "passive"))
      (node (ref "ONOFF") (pin "2") (pinfunction "P_2") (pintype "passive"))
      (node (ref "REG1") (pin "3") (pinfunction "VI_3") (pintype "input"))
    )
    (net (code "54") (name "Net-(PWR-C)") (class "Default")
      (node (ref "PWR") (pin "K") (pinfunction "C_K") (pintype "passive"))
      (node (ref "R8") (pin "1") (pinfunction "1_1") (pintype "passive"))
    )
    (net (code "55") (name "unconnected-(IC3-QH*-Pad9)") (class "Default")
      (node (ref "IC3") (pin "9") (pinfunction "QH*_9") (pintype "tri_state"))
    )
    (net (code "56") (name "unconnected-(ICSP-Pad6)") (class "Default")
      (node (ref "ICSP") (pin "6") (pinfunction "6_6") (pintype "passive"))
    )
    (net (code "57") (name "unconnected-(J1-PadGNDBREAK)") (class "Default")
      (node (ref "J1") (pin "GNDBREAK") (pinfunction "GNDBREAK_GNDBREAK") (pintype "bidirectional"))
    )
    (net (code "58") (name "unconnected-(MIDI_OUT-Pad1)") (class "Default")
      (node (ref "MIDI_OUT") (pin "1") (pinfunction "1_1") (pintype "passive"))
    )
    (net (code "59") (name "unconnected-(MIDI_OUT-Pad2)") (class "Default")
      (node (ref "MIDI_OUT") (pin "2") (pinfunction "2_2") (pintype "passive"))
    )
    (net (code "60") (name "unconnected-(MIDI_OUT-Pad3)") (class "Default")
      (node (ref "MIDI_OUT") (pin "3") (pinfunction "3_3") (pintype "passive"))
    )
    (net (code "61") (name "unconnected-(ONOFF-S-Pad3)") (class "Default")
      (node (ref "ONOFF") (pin "3") (pinfunction "S_3") (pintype "passive"))
    )
  )
)
